# Power.net
KiCad netlist of a schematic drawn in Altium Designer
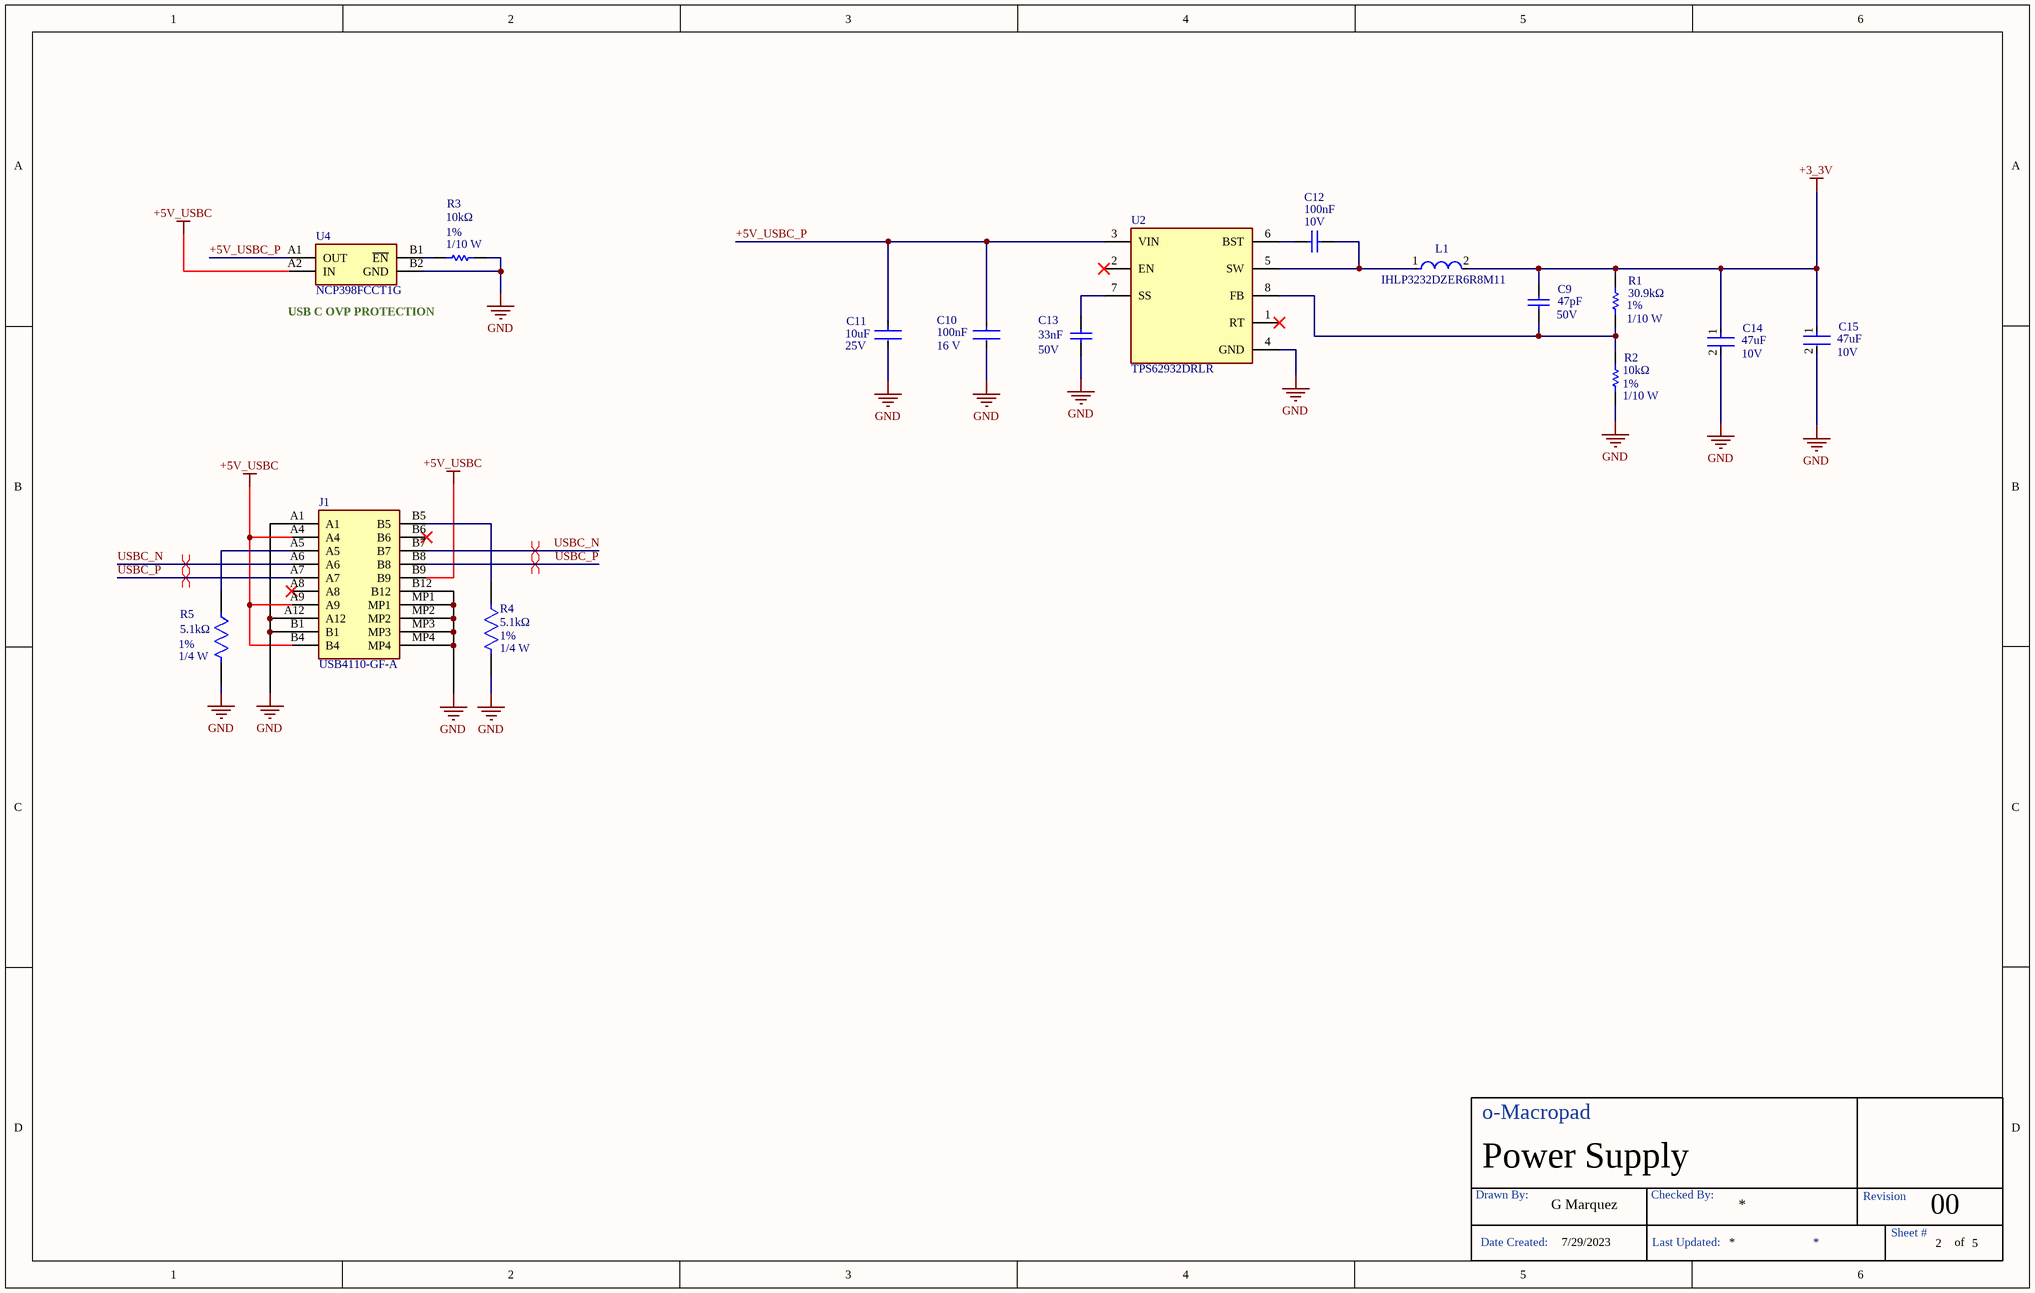
[diagram p0: Power.SchDoc]

(export (version "E")
  (design (tool "Eeschema 10.0.6"))
  (components
    (comp (ref "C9")
      (value "GQM1885C1H470JB01D")
      (footprint "CAPC1608X90X35LL10T15")
      (fields
        (field (name "MANUFACTURER") "Murata")
        (field (name "CAPACITANCE") "47pF")
        (field (name "VOLTAGE RATING") "50V")
      )
      (libsource (lib "Altium Content Vault") (part "CAP"))
    )
    (comp (ref "C10")
      (value "C0603C104K4RACTU")
      (footprint "FP-C0603C-CF-MFG")
      (description "Capacitor; Ceramic; Cap; .100uF; Tol 10%; SMT; Vol-Rtg 16V; X7R; Tape and Reel")
      (fields
        (field (name "CAPACITANCE") "100nF")
        (field (name "VOLTAGE RATING") "16 V")
        (field (name "OCTOPART") "https://octopart.com/c0603c104k4ractu-kemet-93067")
        (field (name "MANUFACTURER") "KEMET")
      )
      (libsource (lib "") (part "b4654b650e69147ec39a6b967a45e02_1"))
    )
    (comp (ref "C11")
      (value "C1608X5R1E106M080AC")
      (footprint "FP-C1608-080-IPC_A")
      (description "CAP CER 10UF 25V X5R 0603")
      (fields
        (field (name "VOLTAGE RATING") "25V")
        (field (name "TOLERANCE") "20%")
        (field (name "CAPACITANCE") "10uF")
      )
      (libsource (lib "Altium Content Vault") (part "11868f565c42a9108669ba33697ecf6"))
    )
    (comp (ref "C12")
      (value "GRM155R71A104KA01D")
      (footprint "CAPC1005X55X25LL05T10")
      (description "Chip Capacitor, 0.1 uF, +/- 10%, 10 V, -55 to 125 degC, 0402 (1005 Metric), RoHS, Tape and Reel")
      (fields
        (field (name "RATED VOLTAGE") "10V")
        (field (name "CAPACITANCE") "100nF")
        (field (name "MANUFACTURER") "Murata")
      )
      (libsource (lib "Altium Content Vault") (part "CAP-NP-2"))
    )
    (comp (ref "C13")
      (value "GRM188R71H333KA61D")
      (footprint "CAPC1608X90X35NL10T15")
      (fields
        (field (name "MANUFACTURER") "Murata")
        (field (name "CAPACITANCE") "33nF")
        (field (name "VOLTAGE RATING") "50V")
      )
      (libsource (lib "Altium Content Vault") (part "CAP"))
    )
    (comp (ref "C14")
      (value "C2012X5R1A476M125AC")
      (footprint "FP-C2012-125-0_2-IPC_B")
      (description "Multilayer Ceramic Capacitors 47μF ±20% 10V X5R SMD 0805")
      (fields
        (field (name "CAPACITANCE") "47uF")
        (field (name "VOLTAGE RATING") "10V")
        (field (name "VOLTAGE") "10V")
        (field (name "TOLERANCE") "20%")
      )
      (libsource (lib "Altium Content Vault") (part "b4654b650e69147ec39a6b967a45e02"))
    )
    (comp (ref "C15")
      (value "C2012X5R1A476M125AC")
      (footprint "FP-C2012-125-0_2-IPC_B")
      (description "Multilayer Ceramic Capacitors 47μF ±20% 10V X5R SMD 0805")
      (fields
        (field (name "CAPACITANCE") "47uF")
        (field (name "VOLTAGE RATING") "10V")
        (field (name "VOLTAGE") "10V")
        (field (name "TOLERANCE") "20%")
      )
      (libsource (lib "Altium Content Vault") (part "b4654b650e69147ec39a6b967a45e02"))
    )
    (comp (ref "J1")
      (value "USB4110-GF-A")
      (footprint "SamacSys:USB4110GFA")
      (description "Connector")
      (libsource (lib "SamacSys") (part "USB4110-GF-A"))
    )
    (comp (ref "L1")
      (value "IHLP3232DZER6R8M11")
      (footprint "FP-IHLP-3232DZ-FP_2_413x5-MFG")
      (description "Commercial Inductors, Low DCR Series 6.8uH 7A 33.4mΩ 20%")
      (fields (field (name "TOLERANCE") "20%"))
      (libsource (lib "Altium Content Vault") (part "725321dda6339637d4d059423bc1c3c"))
    )
    (comp (ref "R1")
      (value "CRCW060330K9FKEA")
      (footprint "RESC1609X50X30LL10T20")
      (fields
        (field (name "MANUFACTURER") "Vishay Dale")
        (field (name "RESISTANCE") "30.9kΩ")
        (field (name "TOLERANCE") "1%")
        (field (name "POWER RATING") "1/10 W")
      )
      (libsource (lib "Altium Content Vault") (part "RES"))
    )
    (comp (ref "R2")
      (value "CRCW060310K0FKEA")
      (footprint "RESC1609X50X30NL8T20")
      (description "Chip Resistor, 10 KOhm, +/- 1%, 100 mW, -55 to 155 degC, 0603 (1608 Metric), RoHS, Tape and Reel")
      (fields
        (field (name "MANUFACTURER") "Vishay Semiconductor")
        (field (name "RESISTANCE") "10kΩ")
        (field (name "TOLERANCE") "1%")
        (field (name "POWER RATING") "1/10 W")
      )
      (libsource (lib "Altium Content Vault") (part "RES-2"))
    )
    (comp (ref "R3")
      (value "CRCW060310K0FKEA")
      (footprint "RESC1609X50X30NL8T20")
      (description "Chip Resistor, 10 KOhm, +/- 1%, 100 mW, -55 to 155 degC, 0603 (1608 Metric), RoHS, Tape and Reel")
      (fields
        (field (name "MANUFACTURER") "Vishay Semiconductor")
        (field (name "RESISTANCE") "10kΩ")
        (field (name "TOLERANCE") "1%")
        (field (name "POWER RATING") "1/10 W")
      )
      (libsource (lib "Altium Content Vault") (part "RES-2"))
    )
    (comp (ref "R4")
      (value "CRCW06035K10FKEAHP")
      (footprint "FP-CRCW0603-HPe3-MFG")
      (description "RES Thick Film, 5.1kΩ, 1%, 0.33W, 100ppm/°C, 0603")
      (fields
        (field (name "TOLERANCE") "1%")
        (field (name "MAX POWER DISSIPATION") "1/4 W")
        (field (name "RESISTANCE") "5.1kΩ")
      )
      (libsource (lib "Altium Content Vault") (part "1029c3af85768c4190bb7ad29bc67b5"))
    )
    (comp (ref "R5")
      (value "CRCW06035K10FKEAHP")
      (footprint "FP-CRCW0603-HPe3-MFG")
      (description "RES Thick Film, 5.1kΩ, 1%, 0.33W, 100ppm/°C, 0603")
      (fields
        (field (name "TOLERANCE") "1%")
        (field (name "MAX POWER DISSIPATION") "1/4 W")
        (field (name "RESISTANCE") "5.1kΩ")
      )
      (libsource (lib "Altium Content Vault") (part "1029c3af85768c4190bb7ad29bc67b5"))
    )
    (comp (ref "U2")
      (value "TPS62932DRLR")
      (footprint "FP-DRL0008A-MFG")
      (description "3.8-V TO 30-V INPUT, 2-A, 200-KH")
      (libsource (lib "Altium Content Vault") (part "530d7937587d685a4b43e131d046c77"))
    )
    (comp (ref "U4")
      (value "NCP398FCCT1G")
      (footprint "SamacSys:BGA4C40P2X2_84X84X60")
      (description "Integrated Circuit")
      (fields (field (name "MOUSER PART NUMBER") "863-NCP398FCCT1G"))
      (libsource (lib "*") (part "NCP398FCCT1G"))
    )
  )
  (nets
    (net (code "1") (name "+3_3V") (class "Default")
      (node (ref "C14") (pin "1") (pinfunction "1_1") (pintype "passive"))
      (node (ref "C15") (pin "1") (pinfunction "1_1") (pintype "passive"))
      (node (ref "C9") (pin "2") (pinfunction "2_2") (pintype "passive"))
      (node (ref "L1") (pin "2") (pinfunction "2_2") (pintype "passive"))
      (node (ref "R1") (pin "2") (pinfunction "2_2") (pintype "passive"))
    )
    (net (code "2") (name "+5V_USBC") (class "Default")
      (node (ref "J1") (pin "A4") (pinfunction "A4_A4") (pintype "passive"))
      (node (ref "J1") (pin "A9") (pinfunction "A9_A9") (pintype "passive"))
      (node (ref "J1") (pin "B4") (pinfunction "B4_B4") (pintype "passive"))
      (node (ref "J1") (pin "B9") (pinfunction "B9_B9") (pintype "passive"))
      (node (ref "U4") (pin "A2") (pinfunction "IN_A2") (pintype "passive"))
    )
    (net (code "3") (name "/+5V_USBC_P") (class "Default")
      (node (ref "C10") (pin "1") (pinfunction "1_1") (pintype "passive"))
      (node (ref "C11") (pin "1") (pinfunction "1_1") (pintype "passive"))
      (node (ref "U2") (pin "3") (pinfunction "VIN_3") (pintype "power_in"))
      (node (ref "U4") (pin "A1") (pinfunction "OUT_A1") (pintype "passive"))
    )
    (net (code "4") (name "/USBC_N") (class "Default")
      (node (ref "J1") (pin "A6") (pinfunction "A6_A6") (pintype "passive"))
      (node (ref "J1") (pin "B7") (pinfunction "B7_B7") (pintype "passive"))
    )
    (net (code "5") (name "/USBC_P") (class "Default")
      (node (ref "J1") (pin "A7") (pinfunction "A7_A7") (pintype "passive"))
      (node (ref "J1") (pin "B8") (pinfunction "B8_B8") (pintype "passive"))
    )
    (net (code "6") (name "GND") (class "Default")
      (node (ref "C10") (pin "2") (pinfunction "2_2") (pintype "passive"))
      (node (ref "C11") (pin "2") (pinfunction "2_2") (pintype "passive"))
      (node (ref "C13") (pin "1") (pinfunction "1_1") (pintype "passive"))
      (node (ref "C14") (pin "2") (pinfunction "2_2") (pintype "passive"))
      (node (ref "C15") (pin "2") (pinfunction "2_2") (pintype "passive"))
      (node (ref "J1") (pin "A1") (pinfunction "A1_A1") (pintype "passive"))
      (node (ref "J1") (pin "A12") (pinfunction "A12_A12") (pintype "passive"))
      (node (ref "J1") (pin "B1") (pinfunction "B1_B1") (pintype "passive"))
      (node (ref "J1") (pin "B12") (pinfunction "B12_B12") (pintype "passive"))
      (node (ref "J1") (pin "MP1") (pinfunction "MP1_MP1") (pintype "passive"))
      (node (ref "J1") (pin "MP2") (pinfunction "MP2_MP2") (pintype "passive"))
      (node (ref "J1") (pin "MP3") (pinfunction "MP3_MP3") (pintype "passive"))
      (node (ref "J1") (pin "MP4") (pinfunction "MP4_MP4") (pintype "passive"))
      (node (ref "R2") (pin "1") (pinfunction "1_1") (pintype "passive"))
      (node (ref "R3") (pin "1") (pinfunction "1_1") (pintype "passive"))
      (node (ref "R4") (pin "2") (pinfunction "2_2") (pintype "passive"))
      (node (ref "R5") (pin "2") (pinfunction "2_2") (pintype "passive"))
      (node (ref "U2") (pin "4") (pinfunction "GND_4") (pintype "power_in"))
      (node (ref "U4") (pin "B2") (pinfunction "GND_B2") (pintype "passive"))
    )
    (net (code "7") (name "Net-(J1-PadA5)") (class "Default")
      (node (ref "J1") (pin "A5") (pinfunction "A5_A5") (pintype "passive"))
      (node (ref "R5") (pin "1") (pinfunction "1_1") (pintype "passive"))
    )
    (net (code "8") (name "Net-(J1-PadB5)") (class "Default")
      (node (ref "J1") (pin "B5") (pinfunction "B5_B5") (pintype "passive"))
      (node (ref "R4") (pin "1") (pinfunction "1_1") (pintype "passive"))
    )
    (net (code "9") (name "Net-(U2-BST)") (class "Default")
      (node (ref "C12") (pin "1") (pinfunction "1_1") (pintype "passive"))
      (node (ref "U2") (pin "6") (pinfunction "BST_6") (pintype "passive"))
    )
    (net (code "10") (name "Net-(U2-FB)") (class "Default")
      (node (ref "C9") (pin "1") (pinfunction "1_1") (pintype "passive"))
      (node (ref "R1") (pin "1") (pinfunction "1_1") (pintype "passive"))
      (node (ref "R2") (pin "2") (pinfunction "2_2") (pintype "passive"))
      (node (ref "U2") (pin "8") (pinfunction "FB_8") (pintype "passive"))
    )
    (net (code "11") (name "Net-(U2-SS)") (class "Default")
      (node (ref "C13") (pin "2") (pinfunction "2_2") (pintype "passive"))
      (node (ref "U2") (pin "7") (pinfunction "SS_7") (pintype "passive"))
    )
    (net (code "12") (name "Net-(U2-SW)") (class "Default")
      (node (ref "C12") (pin "2") (pinfunction "2_2") (pintype "passive"))
      (node (ref "L1") (pin "1") (pinfunction "1_1") (pintype "passive"))
      (node (ref "U2") (pin "5") (pinfunction "SW_5") (pintype "passive"))
    )
    (net (code "13") (name "Net-(U4-~{EN})") (class "Default")
      (node (ref "R3") (pin "2") (pinfunction "2_2") (pintype "passive"))
      (node (ref "U4") (pin "B1") (pinfunction "~{EN}_B1") (pintype "passive"))
    )
    (net (code "14") (name "unconnected-(J1-PadA8)") (class "Default")
      (node (ref "J1") (pin "A8") (pinfunction "A8_A8") (pintype "passive+no_connect"))
    )
    (net (code "15") (name "unconnected-(J1-PadB6)") (class "Default")
      (node (ref "J1") (pin "B6") (pinfunction "B6_B6") (pintype "passive+no_connect"))
    )
    (net (code "16") (name "unconnected-(U2-EN-Pad2)") (class "Default")
      (node (ref "U2") (pin "2") (pinfunction "EN_2") (pintype "passive+no_connect"))
    )
    (net (code "17") (name "unconnected-(U2-RT-Pad1)") (class "Default")
      (node (ref "U2") (pin "1") (pinfunction "RT_1") (pintype "passive+no_connect"))
    )
  )
)
